# ProProject_AT32F403ACGT6_2024-07-07.net
KiCad netlist of a schematic drawn in EasyEDA Pro
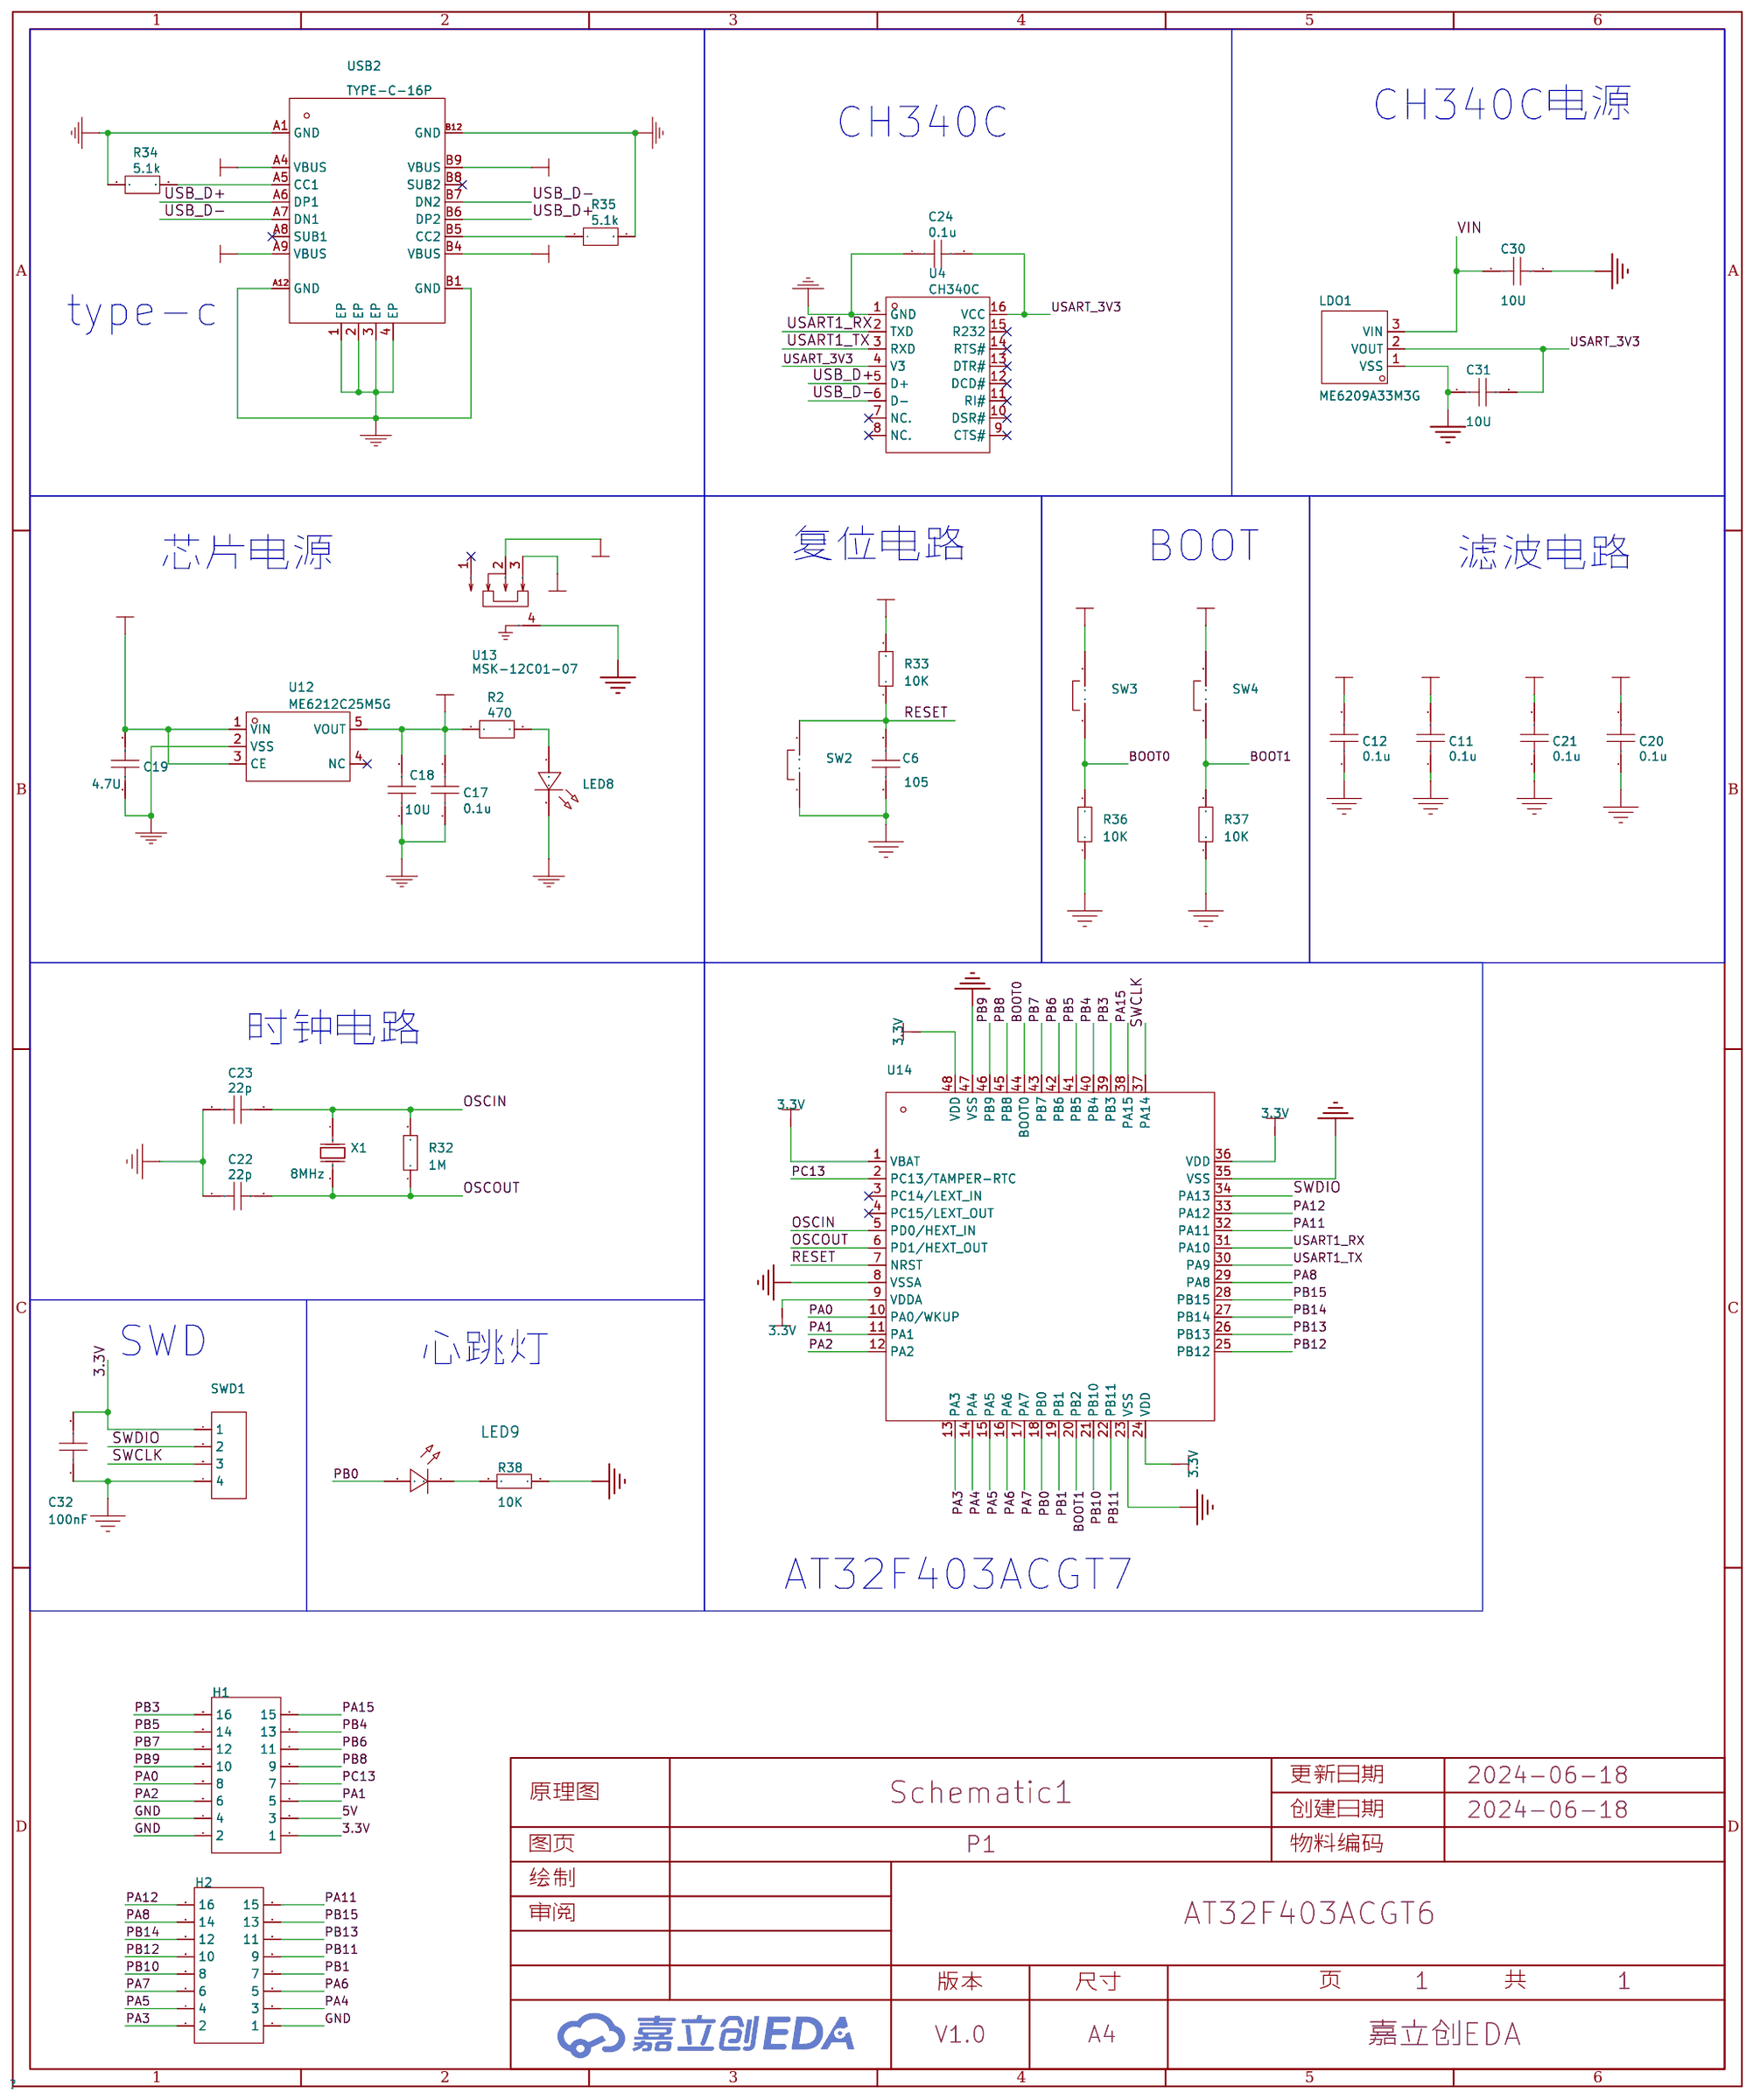
[diagram p0: schematic sheet]

(export (version "E")
  (design (tool "Eeschema 10.0.6"))
  (components
    (comp (ref "C6")
      (value "105")
      (footprint "easyedapro:footprint_88df")
      (libsource (lib "easyedapro") (part "105"))
    )
    (comp (ref "C11")
      (value "0.1u")
      (footprint "easyedapro:footprint_88df")
      (libsource (lib "easyedapro") (part "1u"))
    )
    (comp (ref "C12")
      (value "0.1u")
      (footprint "easyedapro:footprint_88df")
      (libsource (lib "easyedapro") (part "1u"))
    )
    (comp (ref "C17")
      (value "0.1u")
      (footprint "easyedapro:footprint_d063")
      (libsource (lib "easyedapro") (part "0.1u"))
    )
    (comp (ref "C18")
      (value "10U")
      (footprint "easyedapro:footprint_d063")
      (libsource (lib "easyedapro") (part "10U"))
    )
    (comp (ref "C19")
      (value "4.7U")
      (footprint "easyedapro:footprint_d063")
      (libsource (lib "easyedapro") (part "4.7U"))
    )
    (comp (ref "C20")
      (value "0.1u")
      (footprint "easyedapro:footprint_88df")
      (libsource (lib "easyedapro") (part "1u"))
    )
    (comp (ref "C21")
      (value "0.1u")
      (footprint "easyedapro:footprint_88df")
      (libsource (lib "easyedapro") (part "1u"))
    )
    (comp (ref "C22")
      (value "22p")
      (footprint "easyedapro:footprint_88df")
      (libsource (lib "easyedapro") (part "22p"))
    )
    (comp (ref "C23")
      (value "22p")
      (footprint "easyedapro:footprint_88df")
      (libsource (lib "easyedapro") (part "22p"))
    )
    (comp (ref "C24")
      (value "0.1u")
      (footprint "easyedapro:footprint_d063")
      (libsource (lib "easyedapro") (part "0.1u"))
    )
    (comp (ref "C30")
      (value "10U")
      (footprint "easyedapro:C0603")
      (libsource (lib "easyedapro") (part "CapAcitance"))
    )
    (comp (ref "C31")
      (value "10U")
      (footprint "easyedapro:C0603")
      (libsource (lib "easyedapro") (part "CapAcitance"))
    )
    (comp (ref "C32")
      (value "100nF")
      (footprint "easyedapro:C0603")
      (libsource (lib "easyedapro") (part "CapAcitance"))
    )
    (comp (ref "H1")
      (value "~")
      (footprint "easyedapro:HDR-TH_16P-P2.54-V-M-R2-C8-S2.54")
      (libsource (lib "easyedapro") (part "HDR-M-2.54_2x8"))
    )
    (comp (ref "H2")
      (value "~")
      (footprint "easyedapro:HDR-TH_16P-P2.54-V-M-R2-C8-S2.54")
      (libsource (lib "easyedapro") (part "HDR-M-2.54_2x8"))
    )
    (comp (ref "LDO1")
      (value "ME6209A33M3G")
      (footprint "easyedapro:SOT-23-3_L2.9-W1.6-P1.90-LS2.8-BR")
      (description "输出类型:固定;最大输入电压:18V;输出电压:3.3V;最大输出电流:250mA;电源纹波抑制比(PSRR):-;输出极性:正极;")
      (fields (field (name "Manufacturer") "MICRONE(南京微盟)"))
      (libsource (lib "easyedapro") (part "ME6209A33M3G"))
    )
    (comp (ref "LED8")
      (value "LED-0603_R")
      (footprint "easyedapro:footprint_1210")
      (fields
        (field (name "Manufacturer Part") "19-217/R6C-AL1M2VY/3T")
        (field (name "Manufacturer") "EVERLIGHT(台湾亿光)")
      )
      (libsource (lib "easyedapro") (part "LED-0603_R"))
    )
    (comp (ref "LED9")
      (value "~")
      (footprint "easyedapro:LED_0603")
      (libsource (lib "easyedapro") (part "LED_R"))
    )
    (comp (ref "R2")
      (value "470")
      (footprint "easyedapro:footprint_1dde")
      (libsource (lib "easyedapro") (part "470"))
    )
    (comp (ref "R32") (value "1M") (footprint "easyedapro:R0603") (libsource (lib "easyedapro") (part "电阻")))
    (comp (ref "R33") (value "10K") (footprint "easyedapro:R0603") (libsource (lib "easyedapro") (part "电阻")))
    (comp (ref "R34")
      (value "5.1k")
      (footprint "easyedapro:footprint_1dde")
      (libsource (lib "easyedapro") (part "5.1k"))
    )
    (comp (ref "R35")
      (value "5.1k")
      (footprint "easyedapro:footprint_1dde")
      (libsource (lib "easyedapro") (part "5.1k"))
    )
    (comp (ref "R36") (value "10K") (footprint "easyedapro:R0603") (libsource (lib "easyedapro") (part "电阻")))
    (comp (ref "R37") (value "10K") (footprint "easyedapro:R0603") (libsource (lib "easyedapro") (part "电阻")))
    (comp (ref "R38") (value "10K") (footprint "easyedapro:R0603") (libsource (lib "easyedapro") (part "电阻")))
    (comp (ref "SW2")
      (value "3*6*5贴片按键开关")
      (footprint "easyedapro:footprint_ea54")
      (libsource (lib "easyedapro") (part "3*6*5贴片按键开关"))
    )
    (comp (ref "SW3")
      (value "3*6*5贴片按键开关")
      (footprint "easyedapro:footprint_ea54")
      (libsource (lib "easyedapro") (part "3*6*5贴片按键开关"))
    )
    (comp (ref "SW4")
      (value "3*6*5贴片按键开关")
      (footprint "easyedapro:footprint_ea54")
      (libsource (lib "easyedapro") (part "3*6*5贴片按键开关"))
    )
    (comp (ref "SWD1")
      (value "HDR-M-2.54_1x4")
      (footprint "easyedapro:footprint_c5e7")
      (libsource (lib "easyedapro") (part "HDR-M-2.54_1x4"))
    )
    (comp (ref "U4")
      (value "CH340C")
      (footprint "easyedapro:footprint_26da")
      (libsource (lib "easyedapro") (part "CH340C"))
    )
    (comp (ref "U12")
      (value "ME6212C25M5G")
      (footprint "easyedapro:footprint_203e")
      (fields (field (name "Manufacturer") "MICRONE(南京微盟)"))
      (libsource (lib "easyedapro") (part "ME6212C25M5G"))
    )
    (comp (ref "U13")
      (value "MSK-12C01-07")
      (footprint "easyedapro:SW-SMD_MSK12CO2-BDM")
      (libsource (lib "easyedapro") (part "MSK-12C01-07"))
    )
    (comp (ref "U14")
      (value "~")
      (footprint "easyedapro:LQFP-48_L7.0-W7.0-P0.50-LS9.0-BL")
      (description "由官方提供")
      (fields (field (name "Manufacturer") "Artery Technology"))
      (libsource (lib "easyedapro") (part "AT32F403ACxT7"))
    )
    (comp (ref "USB2")
      (value "TYPE-C-16P")
      (footprint "easyedapro:footprint_feef")
      (fields
        (field (name "Manufacturer Part") "KH-TYPE-C-16P")
        (field (name "Manufacturer") "Shenzhen Kinghelm Elec")
      )
      (libsource (lib "easyedapro") (part "TYPE-C-16P"))
    )
    (comp (ref "X1")
      (value "8MHz")
      (footprint "easyedapro:CRYSTAL-SMD_L11.5-W4.8-LS12.7")
      (description "晶振类型:贴片晶振;频率:8MHz;常温频差:±20ppm;外接负载电容:20pF;频率稳定度(全温):±30ppm;")
      (fields (field (name "Manufacturer Part") "X49SM8MSD2SC") (field (name "Manufacturer") "YXC(扬兴晶振)"))
      (libsource (lib "easyedapro") (part "X49SM8MSD2SC"))
    )
  )
  (nets
    (net (code "1") (name "/BOOT0") (class "Default")
      (node (ref "R36") (pin "2") (pinfunction "2_2") (pintype "input"))
      (node (ref "SW3") (pin "1") (pinfunction "1_1") (pintype "unspecified"))
      (node (ref "U14") (pin "44") (pinfunction "BOOT0_44") (pintype "input"))
    )
    (net (code "2") (name "/BOOT1") (class "Default")
      (node (ref "R37") (pin "2") (pinfunction "2_2") (pintype "input"))
      (node (ref "SW4") (pin "1") (pinfunction "1_1") (pintype "unspecified"))
      (node (ref "U14") (pin "20") (pinfunction "PB2_20") (pintype "input"))
    )
    (net (code "3") (name "/OSCIN") (class "Default")
      (node (ref "C23") (pin "2") (pinfunction "2_2") (pintype "unspecified"))
      (node (ref "R32") (pin "2") (pinfunction "2_2") (pintype "input"))
      (node (ref "U14") (pin "5") (pinfunction "PD0/HEXT_IN_5") (pintype "input"))
      (node (ref "X1") (pin "1") (pinfunction "OSC1_1") (pintype "input"))
    )
    (net (code "4") (name "/OSCOUT") (class "Default")
      (node (ref "C22") (pin "2") (pinfunction "2_2") (pintype "unspecified"))
      (node (ref "R32") (pin "1") (pinfunction "1_1") (pintype "input"))
      (node (ref "U14") (pin "6") (pinfunction "PD1/HEXT_OUT_6") (pintype "input"))
      (node (ref "X1") (pin "2") (pinfunction "OSC2_2") (pintype "input"))
    )
    (net (code "5") (name "/PA0") (class "Default")
      (node (ref "H1") (pin "8") (pinfunction "8_8") (pintype "input"))
      (node (ref "U14") (pin "10") (pinfunction "PA0/WKUP_10") (pintype "input"))
    )
    (net (code "6") (name "/PA1") (class "Default")
      (node (ref "H1") (pin "5") (pinfunction "5_5") (pintype "input"))
      (node (ref "U14") (pin "11") (pinfunction "PA1_11") (pintype "input"))
    )
    (net (code "7") (name "/PA2") (class "Default")
      (node (ref "H1") (pin "6") (pinfunction "6_6") (pintype "input"))
      (node (ref "U14") (pin "12") (pinfunction "PA2_12") (pintype "input"))
    )
    (net (code "8") (name "/PA3") (class "Default")
      (node (ref "H2") (pin "2") (pinfunction "2_2") (pintype "input"))
      (node (ref "U14") (pin "13") (pinfunction "PA3_13") (pintype "input"))
    )
    (net (code "9") (name "/PA4") (class "Default")
      (node (ref "H2") (pin "3") (pinfunction "3_3") (pintype "input"))
      (node (ref "U14") (pin "14") (pinfunction "PA4_14") (pintype "input"))
    )
    (net (code "10") (name "/PA5") (class "Default")
      (node (ref "H2") (pin "4") (pinfunction "4_4") (pintype "input"))
      (node (ref "U14") (pin "15") (pinfunction "PA5_15") (pintype "input"))
    )
    (net (code "11") (name "/PA6") (class "Default")
      (node (ref "H2") (pin "5") (pinfunction "5_5") (pintype "input"))
      (node (ref "U14") (pin "16") (pinfunction "PA6_16") (pintype "input"))
    )
    (net (code "12") (name "/PA7") (class "Default")
      (node (ref "H2") (pin "6") (pinfunction "6_6") (pintype "input"))
      (node (ref "U14") (pin "17") (pinfunction "PA7_17") (pintype "input"))
    )
    (net (code "13") (name "/PA8") (class "Default")
      (node (ref "H2") (pin "14") (pinfunction "14_14") (pintype "input"))
      (node (ref "U14") (pin "29") (pinfunction "PA8_29") (pintype "input"))
    )
    (net (code "14") (name "/PA11") (class "Default")
      (node (ref "H2") (pin "15") (pinfunction "15_15") (pintype "input"))
      (node (ref "U14") (pin "32") (pinfunction "PA11_32") (pintype "input"))
    )
    (net (code "15") (name "/PA12") (class "Default")
      (node (ref "H2") (pin "16") (pinfunction "16_16") (pintype "input"))
      (node (ref "U14") (pin "33") (pinfunction "PA12_33") (pintype "input"))
    )
    (net (code "16") (name "/PA15") (class "Default")
      (node (ref "H1") (pin "15") (pinfunction "15_15") (pintype "input"))
      (node (ref "U14") (pin "38") (pinfunction "PA15_38") (pintype "input"))
    )
    (net (code "17") (name "/PB0") (class "Default")
      (node (ref "LED9") (pin "2") (pinfunction "A_2") (pintype "input"))
      (node (ref "U14") (pin "18") (pinfunction "PB0_18") (pintype "input"))
    )
    (net (code "18") (name "/PB1") (class "Default")
      (node (ref "H2") (pin "7") (pinfunction "7_7") (pintype "input"))
      (node (ref "U14") (pin "19") (pinfunction "PB1_19") (pintype "input"))
    )
    (net (code "19") (name "/PB3") (class "Default")
      (node (ref "H1") (pin "16") (pinfunction "16_16") (pintype "input"))
      (node (ref "U14") (pin "39") (pinfunction "PB3_39") (pintype "input"))
    )
    (net (code "20") (name "/PB4") (class "Default")
      (node (ref "H1") (pin "13") (pinfunction "13_13") (pintype "input"))
      (node (ref "U14") (pin "40") (pinfunction "PB4_40") (pintype "input"))
    )
    (net (code "21") (name "/PB5") (class "Default")
      (node (ref "H1") (pin "14") (pinfunction "14_14") (pintype "input"))
      (node (ref "U14") (pin "41") (pinfunction "PB5_41") (pintype "input"))
    )
    (net (code "22") (name "/PB6") (class "Default")
      (node (ref "H1") (pin "11") (pinfunction "11_11") (pintype "input"))
      (node (ref "U14") (pin "42") (pinfunction "PB6_42") (pintype "input"))
    )
    (net (code "23") (name "/PB7") (class "Default")
      (node (ref "H1") (pin "12") (pinfunction "12_12") (pintype "input"))
      (node (ref "U14") (pin "43") (pinfunction "PB7_43") (pintype "input"))
    )
    (net (code "24") (name "/PB8") (class "Default")
      (node (ref "H1") (pin "9") (pinfunction "9_9") (pintype "input"))
      (node (ref "U14") (pin "45") (pinfunction "PB8_45") (pintype "input"))
    )
    (net (code "25") (name "/PB9") (class "Default")
      (node (ref "H1") (pin "10") (pinfunction "10_10") (pintype "input"))
      (node (ref "U14") (pin "46") (pinfunction "PB9_46") (pintype "input"))
    )
    (net (code "26") (name "/PB10") (class "Default")
      (node (ref "H2") (pin "8") (pinfunction "8_8") (pintype "input"))
      (node (ref "U14") (pin "21") (pinfunction "PB10_21") (pintype "input"))
    )
    (net (code "27") (name "/PB11") (class "Default")
      (node (ref "H2") (pin "9") (pinfunction "9_9") (pintype "input"))
      (node (ref "U14") (pin "22") (pinfunction "PB11_22") (pintype "input"))
    )
    (net (code "28") (name "/PB12") (class "Default")
      (node (ref "H2") (pin "10") (pinfunction "10_10") (pintype "input"))
      (node (ref "U14") (pin "25") (pinfunction "PB12_25") (pintype "input"))
    )
    (net (code "29") (name "/PB13") (class "Default")
      (node (ref "H2") (pin "11") (pinfunction "11_11") (pintype "input"))
      (node (ref "U14") (pin "26") (pinfunction "PB13_26") (pintype "input"))
    )
    (net (code "30") (name "/PB14") (class "Default")
      (node (ref "H2") (pin "12") (pinfunction "12_12") (pintype "input"))
      (node (ref "U14") (pin "27") (pinfunction "PB14_27") (pintype "input"))
    )
    (net (code "31") (name "/PB15") (class "Default")
      (node (ref "H2") (pin "13") (pinfunction "13_13") (pintype "input"))
      (node (ref "U14") (pin "28") (pinfunction "PB15_28") (pintype "input"))
    )
    (net (code "32") (name "/PC13") (class "Default")
      (node (ref "H1") (pin "7") (pinfunction "7_7") (pintype "input"))
      (node (ref "U14") (pin "2") (pinfunction "PC13/TAMPER-RTC_2") (pintype "input"))
    )
    (net (code "33") (name "/RESET") (class "Default")
      (node (ref "C6") (pin "2") (pinfunction "2_2") (pintype "unspecified"))
      (node (ref "R33") (pin "1") (pinfunction "1_1") (pintype "input"))
      (node (ref "SW2") (pin "2") (pinfunction "2_2") (pintype "unspecified"))
      (node (ref "U14") (pin "7") (pinfunction "NRST_7") (pintype "input"))
    )
    (net (code "34") (name "/SWCLK") (class "Default")
      (node (ref "SWD1") (pin "3") (pinfunction "3_3") (pintype "unspecified"))
      (node (ref "U14") (pin "37") (pinfunction "PA14_37") (pintype "input"))
    )
    (net (code "35") (name "/SWDIO") (class "Default")
      (node (ref "SWD1") (pin "2") (pinfunction "2_2") (pintype "unspecified"))
      (node (ref "U14") (pin "34") (pinfunction "PA13_34") (pintype "input"))
    )
    (net (code "36") (name "/USART1_RX") (class "Default")
      (node (ref "U14") (pin "31") (pinfunction "PA10_31") (pintype "input"))
      (node (ref "U4") (pin "2") (pinfunction "TXD_2") (pintype "unspecified"))
    )
    (net (code "37") (name "/USART1_TX") (class "Default")
      (node (ref "U14") (pin "30") (pinfunction "PA9_30") (pintype "input"))
      (node (ref "U4") (pin "3") (pinfunction "RXD_3") (pintype "unspecified"))
    )
    (net (code "38") (name "/USART_3V3") (class "Default")
      (node (ref "C24") (pin "2") (pinfunction "2_2") (pintype "unspecified"))
      (node (ref "C31") (pin "2") (pinfunction "2_2") (pintype "input"))
      (node (ref "LDO1") (pin "2") (pinfunction "VOUT_2") (pintype "unspecified"))
      (node (ref "U4") (pin "16") (pinfunction "VCC_16") (pintype "unspecified"))
      (node (ref "U4") (pin "4") (pinfunction "V3_4") (pintype "unspecified"))
    )
    (net (code "39") (name "/USB_D+") (class "Default")
      (node (ref "U4") (pin "5") (pinfunction "D+_5") (pintype "unspecified"))
      (node (ref "USB2") (pin "A6") (pinfunction "DP1_A6") (pintype "unspecified"))
      (node (ref "USB2") (pin "B6") (pinfunction "DP2_B6") (pintype "unspecified"))
    )
    (net (code "40") (name "/USB_D-") (class "Default")
      (node (ref "U4") (pin "6") (pinfunction "D-_6") (pintype "unspecified"))
      (node (ref "USB2") (pin "A7") (pinfunction "DN1_A7") (pintype "unspecified"))
      (node (ref "USB2") (pin "B7") (pinfunction "DN2_B7") (pintype "unspecified"))
    )
    (net (code "41") (name "3.3V") (class "Default")
      (node (ref "C11") (pin "2") (pinfunction "2_2") (pintype "unspecified"))
      (node (ref "C12") (pin "2") (pinfunction "2_2") (pintype "unspecified"))
      (node (ref "C17") (pin "2") (pinfunction "2_2") (pintype "unspecified"))
      (node (ref "C18") (pin "2") (pinfunction "2_2") (pintype "unspecified"))
      (node (ref "C20") (pin "2") (pinfunction "2_2") (pintype "unspecified"))
      (node (ref "C21") (pin "2") (pinfunction "2_2") (pintype "unspecified"))
      (node (ref "C32") (pin "2") (pinfunction "2_2") (pintype "input"))
      (node (ref "H1") (pin "1") (pinfunction "1_1") (pintype "input"))
      (node (ref "R2") (pin "1") (pinfunction "1_1") (pintype "unspecified"))
      (node (ref "R33") (pin "2") (pinfunction "2_2") (pintype "input"))
      (node (ref "SW3") (pin "2") (pinfunction "2_2") (pintype "unspecified"))
      (node (ref "SW4") (pin "2") (pinfunction "2_2") (pintype "unspecified"))
      (node (ref "SWD1") (pin "1") (pinfunction "1_1") (pintype "unspecified"))
      (node (ref "U12") (pin "5") (pinfunction "VOUT_5") (pintype "unspecified"))
      (node (ref "U14") (pin "1") (pinfunction "VBAT_1") (pintype "input"))
      (node (ref "U14") (pin "24") (pinfunction "VDD_24") (pintype "input"))
      (node (ref "U14") (pin "36") (pinfunction "VDD_36") (pintype "input"))
      (node (ref "U14") (pin "48") (pinfunction "VDD_48") (pintype "input"))
      (node (ref "U14") (pin "9") (pinfunction "VDDA_9") (pintype "input"))
    )
    (net (code "42") (name "5V") (class "Default")
      (node (ref "C19") (pin "2") (pinfunction "2_2") (pintype "unspecified"))
      (node (ref "H1") (pin "3") (pinfunction "3_3") (pintype "input"))
      (node (ref "U12") (pin "1") (pinfunction "VIN_1") (pintype "unspecified"))
      (node (ref "U12") (pin "3") (pinfunction "CE_3") (pintype "unspecified"))
      (node (ref "U13") (pin "2") (pinfunction "2_2") (pintype "input"))
    )
    (net (code "43") (name "GND") (class "Default")
      (node (ref "C11") (pin "1") (pinfunction "1_1") (pintype "unspecified"))
      (node (ref "C12") (pin "1") (pinfunction "1_1") (pintype "unspecified"))
      (node (ref "C17") (pin "1") (pinfunction "1_1") (pintype "unspecified"))
      (node (ref "C18") (pin "1") (pinfunction "1_1") (pintype "unspecified"))
      (node (ref "C19") (pin "1") (pinfunction "1_1") (pintype "unspecified"))
      (node (ref "C20") (pin "1") (pinfunction "1_1") (pintype "unspecified"))
      (node (ref "C21") (pin "1") (pinfunction "1_1") (pintype "unspecified"))
      (node (ref "C22") (pin "1") (pinfunction "1_1") (pintype "unspecified"))
      (node (ref "C23") (pin "1") (pinfunction "1_1") (pintype "unspecified"))
      (node (ref "C24") (pin "1") (pinfunction "1_1") (pintype "unspecified"))
      (node (ref "C30") (pin "2") (pinfunction "2_2") (pintype "input"))
      (node (ref "C31") (pin "1") (pinfunction "1_1") (pintype "input"))
      (node (ref "C32") (pin "1") (pinfunction "1_1") (pintype "input"))
      (node (ref "C6") (pin "1") (pinfunction "1_1") (pintype "unspecified"))
      (node (ref "H1") (pin "2") (pinfunction "2_2") (pintype "input"))
      (node (ref "H1") (pin "4") (pinfunction "4_4") (pintype "input"))
      (node (ref "H2") (pin "1") (pinfunction "1_1") (pintype "input"))
      (node (ref "LDO1") (pin "1") (pinfunction "VSS_1") (pintype "unspecified"))
      (node (ref "LED8") (pin "2") (pinfunction "2_2") (pintype "unspecified"))
      (node (ref "R34") (pin "1") (pinfunction "1_1") (pintype "unspecified"))
      (node (ref "R35") (pin "2") (pinfunction "2_2") (pintype "unspecified"))
      (node (ref "R36") (pin "1") (pinfunction "1_1") (pintype "input"))
      (node (ref "R37") (pin "1") (pinfunction "1_1") (pintype "input"))
      (node (ref "R38") (pin "2") (pinfunction "2_2") (pintype "input"))
      (node (ref "SW2") (pin "1") (pinfunction "1_1") (pintype "unspecified"))
      (node (ref "SWD1") (pin "4") (pinfunction "4_4") (pintype "unspecified"))
      (node (ref "U12") (pin "2") (pinfunction "VSS_2") (pintype "unspecified"))
      (node (ref "U13") (pin "4") (pinfunction "4_4") (pintype "input"))
      (node (ref "U14") (pin "23") (pinfunction "VSS_23") (pintype "input"))
      (node (ref "U14") (pin "35") (pinfunction "VSS_35") (pintype "input"))
      (node (ref "U14") (pin "47") (pinfunction "VSS_47") (pintype "input"))
      (node (ref "U14") (pin "8") (pinfunction "VSSA_8") (pintype "input"))
      (node (ref "U4") (pin "1") (pinfunction "GND_1") (pintype "unspecified"))
      (node (ref "USB2") (pin "1") (pinfunction "EP_1") (pintype "unspecified"))
      (node (ref "USB2") (pin "2") (pinfunction "EP_2") (pintype "unspecified"))
      (node (ref "USB2") (pin "3") (pinfunction "EP_3") (pintype "unspecified"))
      (node (ref "USB2") (pin "4") (pinfunction "EP_4") (pintype "unspecified"))
      (node (ref "USB2") (pin "A1") (pinfunction "GND_A1") (pintype "unspecified"))
      (node (ref "USB2") (pin "A12") (pinfunction "GND_A12") (pintype "unspecified"))
      (node (ref "USB2") (pin "B1") (pinfunction "GND_B1") (pintype "unspecified"))
      (node (ref "USB2") (pin "B12") (pinfunction "GND_B12") (pintype "unspecified"))
    )
    (net (code "44") (name "Net-(LED8-Pad1)") (class "Default")
      (node (ref "LED8") (pin "1") (pinfunction "1_1") (pintype "unspecified"))
      (node (ref "R2") (pin "2") (pinfunction "2_2") (pintype "unspecified"))
    )
    (net (code "45") (name "Net-(LED9-C)") (class "Default")
      (node (ref "LED9") (pin "1") (pinfunction "C_1") (pintype "input"))
      (node (ref "R38") (pin "1") (pinfunction "1_1") (pintype "input"))
    )
    (net (code "46") (name "Net-(USB2-CC1)") (class "Default")
      (node (ref "R34") (pin "2") (pinfunction "2_2") (pintype "unspecified"))
      (node (ref "USB2") (pin "A5") (pinfunction "CC1_A5") (pintype "unspecified"))
    )
    (net (code "47") (name "Net-(USB2-CC2)") (class "Default")
      (node (ref "R35") (pin "1") (pinfunction "1_1") (pintype "unspecified"))
      (node (ref "USB2") (pin "B5") (pinfunction "CC2_B5") (pintype "unspecified"))
    )
    (net (code "48") (name "VIN") (class "Default")
      (node (ref "C30") (pin "1") (pinfunction "1_1") (pintype "input"))
      (node (ref "LDO1") (pin "3") (pinfunction "VIN_3") (pintype "unspecified"))
      (node (ref "U13") (pin "3") (pinfunction "3_3") (pintype "input"))
      (node (ref "USB2") (pin "A4") (pinfunction "VBUS_A4") (pintype "unspecified"))
      (node (ref "USB2") (pin "A9") (pinfunction "VBUS_A9") (pintype "unspecified"))
      (node (ref "USB2") (pin "B4") (pinfunction "VBUS_B4") (pintype "unspecified"))
      (node (ref "USB2") (pin "B9") (pinfunction "VBUS_B9") (pintype "unspecified"))
    )
    (net (code "49") (name "unconnected-(U4-CTS#-Pad9)") (class "Default")
      (node (ref "U4") (pin "9") (pinfunction "CTS#_9") (pintype "unspecified+no_connect"))
    )
    (net (code "50") (name "unconnected-(U4-DCD#-Pad12)") (class "Default")
      (node (ref "U4") (pin "12") (pinfunction "DCD#_12") (pintype "unspecified+no_connect"))
    )
    (net (code "51") (name "unconnected-(U4-DSR#-Pad10)") (class "Default")
      (node (ref "U4") (pin "10") (pinfunction "DSR#_10") (pintype "unspecified+no_connect"))
    )
    (net (code "52") (name "unconnected-(U4-DTR#-Pad13)") (class "Default")
      (node (ref "U4") (pin "13") (pinfunction "DTR#_13") (pintype "unspecified+no_connect"))
    )
    (net (code "53") (name "unconnected-(U4-NC.-Pad7)") (class "Default")
      (node (ref "U4") (pin "7") (pinfunction "NC._7") (pintype "unspecified+no_connect"))
    )
    (net (code "54") (name "unconnected-(U4-NC.-Pad8)") (class "Default")
      (node (ref "U4") (pin "8") (pinfunction "NC._8") (pintype "unspecified+no_connect"))
    )
    (net (code "55") (name "unconnected-(U4-R232-Pad15)") (class "Default")
      (node (ref "U4") (pin "15") (pinfunction "R232_15") (pintype "unspecified+no_connect"))
    )
    (net (code "56") (name "unconnected-(U4-RI#-Pad11)") (class "Default")
      (node (ref "U4") (pin "11") (pinfunction "RI#_11") (pintype "unspecified+no_connect"))
    )
    (net (code "57") (name "unconnected-(U4-RTS#-Pad14)") (class "Default")
      (node (ref "U4") (pin "14") (pinfunction "RTS#_14") (pintype "unspecified+no_connect"))
    )
    (net (code "58") (name "unconnected-(U12-NC-Pad4)") (class "Default")
      (node (ref "U12") (pin "4") (pinfunction "NC_4") (pintype "unspecified+no_connect"))
    )
    (net (code "59") (name "unconnected-(U13-Pad1)") (class "Default")
      (node (ref "U13") (pin "1") (pinfunction "1_1") (pintype "input+no_connect"))
    )
    (net (code "60") (name "unconnected-(U14-PC14{slash}LEXT_IN-Pad3)") (class "Default")
      (node (ref "U14") (pin "3") (pinfunction "PC14/LEXT_IN_3") (pintype "input+no_connect"))
    )
    (net (code "61") (name "unconnected-(U14-PC15{slash}LEXT_OUT-Pad4)") (class "Default")
      (node (ref "U14") (pin "4") (pinfunction "PC15/LEXT_OUT_4") (pintype "input+no_connect"))
    )
    (net (code "62") (name "unconnected-(USB2-SUB1-PadA8)") (class "Default")
      (node (ref "USB2") (pin "A8") (pinfunction "SUB1_A8") (pintype "unspecified+no_connect"))
    )
    (net (code "63") (name "unconnected-(USB2-SUB2-PadB8)") (class "Default")
      (node (ref "USB2") (pin "B8") (pinfunction "SUB2_B8") (pintype "unspecified+no_connect"))
    )
  )
)
